# R14FANEXT_ok.net
KiCad netlist of a schematic drawn in Altium Designer
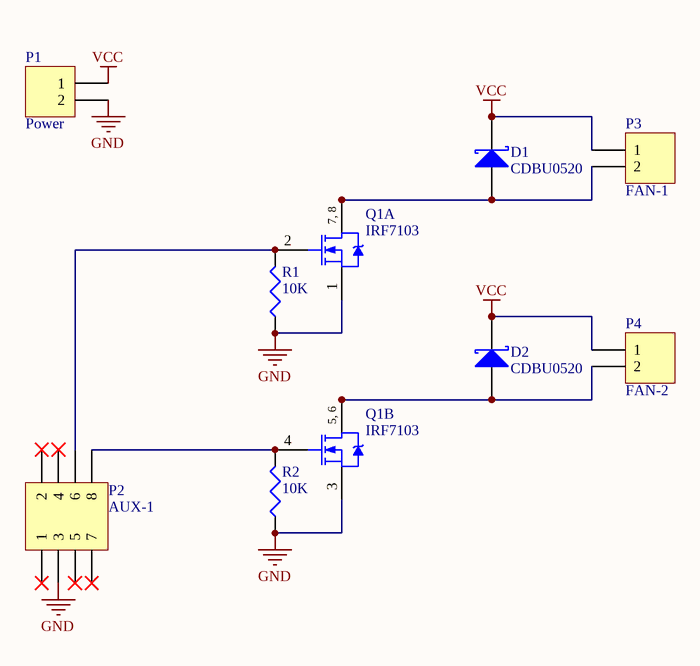
[diagram p0: R14FANEXT_ok.SchDoc]

(export (version "E")
  (design (tool "Eeschema 10.0.6"))
  (components
    (comp (ref "D1")
      (value "CDBU0520")
      (footprint "DIOM1709X09N")
      (description "Schottky Diode")
      (fields (field (name "PUBLISHER") "Altium Limited"))
      (libsource (lib "Miscellaneous Devices") (part "D Schottky"))
    )
    (comp (ref "D2")
      (value "CDBU0520")
      (footprint "DIOM1709X09N")
      (description "Schottky Diode")
      (fields (field (name "PUBLISHER") "Altium Limited"))
      (libsource (lib "Miscellaneous Devices") (part "D Schottky"))
    )
    (comp (ref "P1")
      (value "Power")
      (footprint "HDR1X2")
      (description "Header, 2-Pin")
      (fields (field (name "PUBLISHER") "Altium Limited"))
      (libsource (lib "") (part "Header 2_1"))
    )
    (comp (ref "P2")
      (value "AUX-1")
      (footprint "HDR2X4")
      (description "Header, 4-Pin, Dual row")
      (fields (field (name "PUBLISHER") "Altium Limited"))
      (libsource (lib "Miscellaneous Connectors") (part "Header 4X2"))
    )
    (comp (ref "P3")
      (value "FAN-1")
      (footprint "HDR1X2")
      (description "Header, 2-Pin")
      (fields (field (name "PUBLISHER") "Altium Limited"))
      (libsource (lib "Miscellaneous Connectors") (part "Header 2"))
    )
    (comp (ref "P4")
      (value "FAN-2")
      (footprint "HDR1X2")
      (description "Header, 2-Pin")
      (fields (field (name "PUBLISHER") "Altium Limited"))
      (libsource (lib "Miscellaneous Connectors") (part "Header 2"))
    )
    (comp (ref "Q1")
      (value "IRF7103")
      (footprint "SO-8_N")
      (description "HEXFET Power MOSFET")
      (fields (field (name "PUBLISHER") "Altium Limited"))
      (libsource (lib "IR Discrete MOSFET - Power") (part "IRF7103"))
    )
    (comp (ref "R1")
      (value "10K")
      (footprint "J1-0603")
      (description "Resistor")
      (fields (field (name "Comment") "Res3") (field (name "PUBLISHER") "Altium Limited"))
      (libsource (lib "Miscellaneous Devices") (part "Res3"))
    )
    (comp (ref "R2")
      (value "10K")
      (footprint "J1-0603")
      (description "Resistor")
      (fields (field (name "Comment") "Res3") (field (name "PUBLISHER") "Altium Limited"))
      (libsource (lib "Miscellaneous Devices") (part "Res3"))
    )
  )
  (nets
    (net (code "1") (name "GND") (class "Default")
      (node (ref "P1") (pin "2") (pinfunction "2_2") (pintype "passive"))
      (node (ref "P2") (pin "3") (pinfunction "3_3") (pintype "passive"))
      (node (ref "Q1") (pin "1") (pinfunction "S_1") (pintype "passive"))
      (node (ref "Q1") (pin "3") (pinfunction "S_3") (pintype "passive"))
      (node (ref "R1") (pin "1") (pinfunction "1_1") (pintype "passive"))
      (node (ref "R2") (pin "1") (pinfunction "1_1") (pintype "passive"))
    )
    (net (code "2") (name "Net-(D1-A)") (class "Default")
      (node (ref "D1") (pin "1") (pinfunction "A_1") (pintype "passive"))
      (node (ref "P3") (pin "2") (pinfunction "2_2") (pintype "passive"))
      (node (ref "Q1") (pin "7") (pinfunction "D_7") (pintype "passive"))
      (node (ref "Q1") (pin "8") (pinfunction "D_8") (pintype "passive"))
    )
    (net (code "3") (name "Net-(D2-A)") (class "Default")
      (node (ref "D2") (pin "1") (pinfunction "A_1") (pintype "passive"))
      (node (ref "P4") (pin "2") (pinfunction "2_2") (pintype "passive"))
      (node (ref "Q1") (pin "5") (pinfunction "D_5") (pintype "passive"))
      (node (ref "Q1") (pin "6") (pinfunction "D_6") (pintype "passive"))
    )
    (net (code "4") (name "Net-(Q1A-G)") (class "Default")
      (node (ref "P2") (pin "6") (pinfunction "6_6") (pintype "passive"))
      (node (ref "Q1") (pin "2") (pinfunction "G_2") (pintype "passive"))
      (node (ref "R1") (pin "2") (pinfunction "2_2") (pintype "passive"))
    )
    (net (code "5") (name "Net-(Q1B-G)") (class "Default")
      (node (ref "P2") (pin "8") (pinfunction "8_8") (pintype "passive"))
      (node (ref "Q1") (pin "4") (pinfunction "G_4") (pintype "passive"))
      (node (ref "R2") (pin "2") (pinfunction "2_2") (pintype "passive"))
    )
    (net (code "6") (name "VCC") (class "Default")
      (node (ref "D1") (pin "2") (pinfunction "K_2") (pintype "passive"))
      (node (ref "D2") (pin "2") (pinfunction "K_2") (pintype "passive"))
      (node (ref "P1") (pin "1") (pinfunction "1_1") (pintype "passive"))
      (node (ref "P3") (pin "1") (pinfunction "1_1") (pintype "passive"))
      (node (ref "P4") (pin "1") (pinfunction "1_1") (pintype "passive"))
    )
    (net (code "7") (name "unconnected-(P2-Pad1)") (class "Default")
      (node (ref "P2") (pin "1") (pinfunction "1_1") (pintype "passive+no_connect"))
    )
    (net (code "8") (name "unconnected-(P2-Pad2)") (class "Default")
      (node (ref "P2") (pin "2") (pinfunction "2_2") (pintype "passive+no_connect"))
    )
    (net (code "9") (name "unconnected-(P2-Pad4)") (class "Default")
      (node (ref "P2") (pin "4") (pinfunction "4_4") (pintype "passive+no_connect"))
    )
    (net (code "10") (name "unconnected-(P2-Pad5)") (class "Default")
      (node (ref "P2") (pin "5") (pinfunction "5_5") (pintype "passive+no_connect"))
    )
    (net (code "11") (name "unconnected-(P2-Pad7)") (class "Default")
      (node (ref "P2") (pin "7") (pinfunction "7_7") (pintype "passive+no_connect"))
    )
  )
)
